# SD_Card.net
KiCad netlist of a schematic drawn in Altium Designer
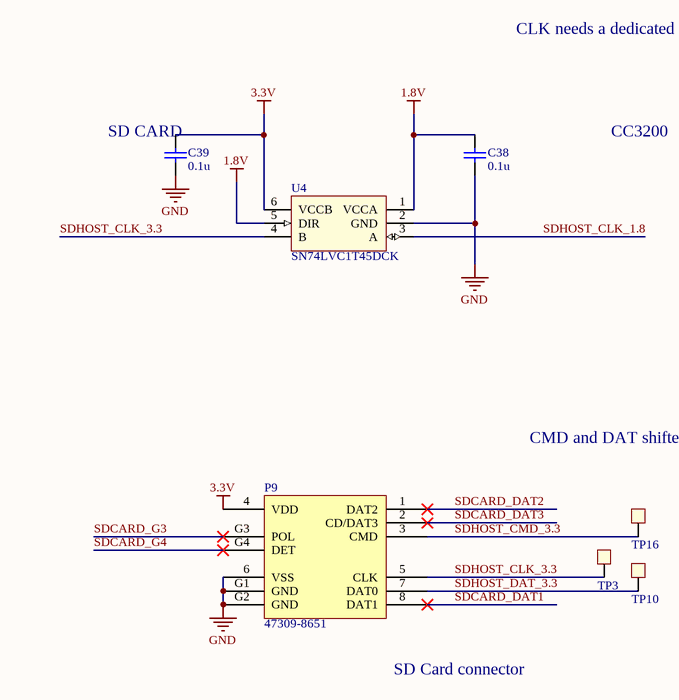
[diagram p0: SD_Card.SchDoc]

(export (version "E")
  (design (tool "Eeschema 10.0.6"))
  (components
    (comp (ref "C38")
      (value "0.1u")
      (footprint "CAP0402_SENSE_DVT")
      (description "Chip capacitor")
      (fields (field (name "TOLERANCE") "10%") (field (name "VOLTAGE") "50V"))
      (libsource (lib "Morpheus_pill") (part "C_0.1u_10_50_X7R_0402"))
    )
    (comp (ref "C39")
      (value "0.1u")
      (footprint "CAP0402_SENSE_DVT")
      (description "Chip capacitor")
      (fields (field (name "TOLERANCE") "10%") (field (name "VOLTAGE") "50V"))
      (libsource (lib "Morpheus_pill") (part "C_0.1u_10_50_X7R_0402"))
    )
    (comp (ref "P9")
      (value "47309-8651")
      (footprint "molex_47309-8651")
      (description "Molex SD card connector")
      (libsource (lib "Morpheus_pill") (part "molex_47309-8651"))
    )
    (comp (ref "TP3")
      (value "TP")
      (footprint "TP-1.1")
      (description "testpoint")
      (libsource (lib "Morpheus_pill") (part "TP"))
    )
    (comp (ref "TP10")
      (value "TP")
      (footprint "TP-1.1")
      (description "testpoint")
      (libsource (lib "Morpheus_pill") (part "TP"))
    )
    (comp (ref "TP16")
      (value "TP")
      (footprint "TP-1.1")
      (description "testpoint")
      (libsource (lib "Morpheus_pill") (part "TP"))
    )
    (comp (ref "U4")
      (value "SN74LVC1T45DCK")
      (footprint "SC-70-6")
      (description "Single-bit dual-supply bus transceiver")
      (libsource (lib "Morpheus_pill") (part "SN74LVC1T45DCK"))
    )
  )
  (nets
    (net (code "1") (name "/SDCARD_DAT1") (class "Default")
      (node (ref "P9") (pin "8") (pinfunction "DAT1_8") (pintype "passive+no_connect"))
    )
    (net (code "2") (name "/SDCARD_DAT2") (class "Default")
      (node (ref "P9") (pin "1") (pinfunction "DAT2_1") (pintype "passive+no_connect"))
    )
    (net (code "3") (name "/SDCARD_DAT3") (class "Default")
      (node (ref "P9") (pin "2") (pinfunction "CD/DAT3_2") (pintype "passive+no_connect"))
    )
    (net (code "4") (name "/SDCARD_G3") (class "Default")
      (node (ref "P9") (pin "G3") (pinfunction "POL_G3") (pintype "passive+no_connect"))
    )
    (net (code "5") (name "/SDCARD_G4") (class "Default")
      (node (ref "P9") (pin "G4") (pinfunction "DET_G4") (pintype "passive+no_connect"))
    )
    (net (code "6") (name "/SDHOST_CLK_1.8") (class "Default")
      (node (ref "U4") (pin "3") (pinfunction "A_3") (pintype "bidirectional"))
    )
    (net (code "7") (name "/SDHOST_CLK_3.3") (class "Default")
      (node (ref "P9") (pin "5") (pinfunction "CLK_5") (pintype "passive"))
      (node (ref "TP3") (pin "1") (pinfunction "1_1") (pintype "passive"))
      (node (ref "U4") (pin "4") (pinfunction "B_4") (pintype "power_in"))
    )
    (net (code "8") (name "/SDHOST_CMD_3.3") (class "Default")
      (node (ref "P9") (pin "3") (pinfunction "CMD_3") (pintype "passive"))
      (node (ref "TP16") (pin "1") (pinfunction "1_1") (pintype "passive"))
    )
    (net (code "9") (name "/SDHOST_DAT_3.3") (class "Default")
      (node (ref "P9") (pin "7") (pinfunction "DAT0_7") (pintype "passive"))
      (node (ref "TP10") (pin "1") (pinfunction "1_1") (pintype "passive"))
    )
    (net (code "10") (name "1.8V") (class "Default")
      (node (ref "C38") (pin "2") (pinfunction "2_2") (pintype "passive"))
      (node (ref "U4") (pin "1") (pinfunction "VCCA_1") (pintype "power_in"))
      (node (ref "U4") (pin "5") (pinfunction "DIR_5") (pintype "input"))
    )
    (net (code "11") (name "3.3V") (class "Default")
      (node (ref "C39") (pin "2") (pinfunction "2_2") (pintype "passive"))
      (node (ref "P9") (pin "4") (pinfunction "VDD_4") (pintype "power_in"))
      (node (ref "U4") (pin "6") (pinfunction "VCCB_6") (pintype "power_in"))
    )
    (net (code "12") (name "GND") (class "Default")
      (node (ref "C38") (pin "1") (pinfunction "1_1") (pintype "passive"))
      (node (ref "C39") (pin "1") (pinfunction "1_1") (pintype "passive"))
      (node (ref "P9") (pin "6") (pinfunction "VSS_6") (pintype "power_in"))
      (node (ref "P9") (pin "G1") (pinfunction "GND_G1") (pintype "power_in"))
      (node (ref "P9") (pin "G2") (pinfunction "GND_G2") (pintype "power_in"))
      (node (ref "U4") (pin "2") (pinfunction "GND_2") (pintype "power_in"))
    )
  )
)
